# throughHoleAdapterTransistor.net
KiCad netlist of a schematic drawn in EAGLE
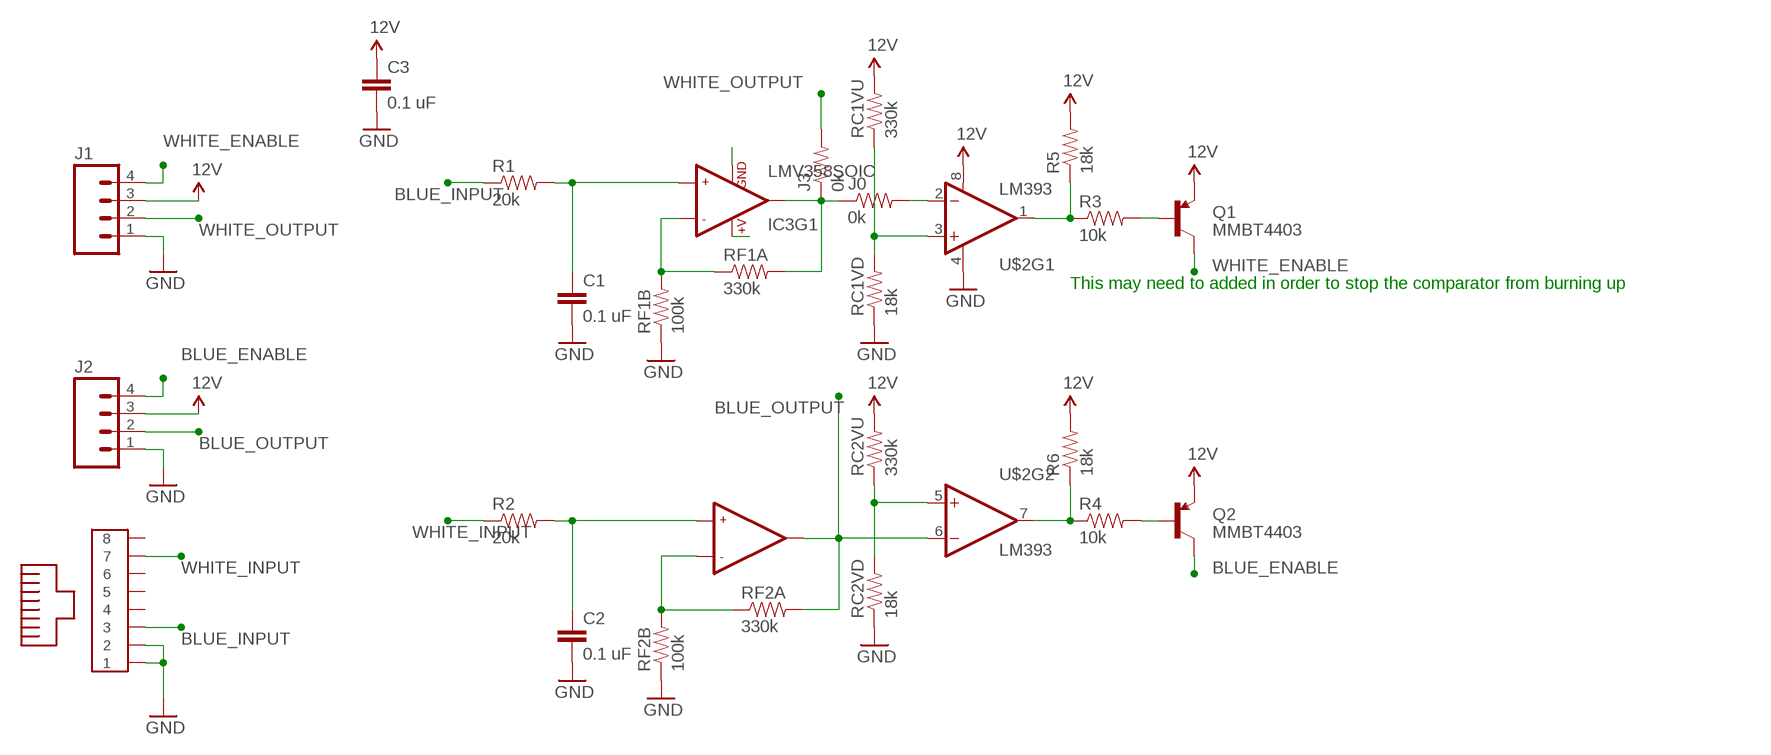
[diagram p0: schematic, sheet 1]

(export (version "E")
  (design (tool "Eeschema 10.0.6"))
  (components
    (comp (ref "C1")
      (value "0.1 uF")
      (footprint "eagle-import:1206")
      (libsource (lib "eagle-import") (part "CAP1206"))
    )
    (comp (ref "C2")
      (value "0.1 uF")
      (footprint "eagle-import:1206")
      (libsource (lib "eagle-import") (part "CAP1206"))
    )
    (comp (ref "C3")
      (value "0.1 uF")
      (footprint "eagle-import:1206")
      (libsource (lib "eagle-import") (part "CAP1206"))
    )
    (comp (ref "IC3")
      (value "LMV358SOIC")
      (footprint "eagle-import:SO08")
      (libsource (lib "eagle-import") (part "LMV358SOIC"))
    )
    (comp (ref "J0")
      (value "0k")
      (footprint "eagle-import:1206")
      (libsource (lib "eagle-import") (part "RESISTOR1206"))
    )
    (comp (ref "J1")
      (value "M04LONGPADS")
      (footprint "eagle-import:1X04_LONGPADS")
      (libsource (lib "eagle-import") (part "M04LONGPADS"))
    )
    (comp (ref "J2")
      (value "M04LONGPADS")
      (footprint "eagle-import:1X04_LONGPADS")
      (libsource (lib "eagle-import") (part "M04LONGPADS"))
    )
    (comp (ref "J3")
      (value "0k")
      (footprint "eagle-import:1206")
      (libsource (lib "eagle-import") (part "RESISTOR1206"))
    )
    (comp (ref "Q1")
      (value "MMBT4403")
      (footprint "eagle-import:SOT23-3")
      (libsource (lib "eagle-import") (part "TRANSISTOR_PNPMMBT4403"))
    )
    (comp (ref "Q2")
      (value "MMBT4403")
      (footprint "eagle-import:SOT23-3")
      (libsource (lib "eagle-import") (part "TRANSISTOR_PNPMMBT4403"))
    )
    (comp (ref "R1")
      (value "20k")
      (footprint "eagle-import:1206")
      (libsource (lib "eagle-import") (part "RESISTOR1206"))
    )
    (comp (ref "R2")
      (value "20k")
      (footprint "eagle-import:1206")
      (libsource (lib "eagle-import") (part "RESISTOR1206"))
    )
    (comp (ref "R3")
      (value "10k")
      (footprint "eagle-import:1206")
      (libsource (lib "eagle-import") (part "RESISTOR1206"))
    )
    (comp (ref "R4")
      (value "10k")
      (footprint "eagle-import:1206")
      (libsource (lib "eagle-import") (part "RESISTOR1206"))
    )
    (comp (ref "R5")
      (value "18k")
      (footprint "eagle-import:1206")
      (libsource (lib "eagle-import") (part "RESISTOR1206"))
    )
    (comp (ref "R6")
      (value "18k")
      (footprint "eagle-import:1206")
      (libsource (lib "eagle-import") (part "RESISTOR1206"))
    )
    (comp (ref "RC1VD")
      (value "18k")
      (footprint "eagle-import:1206")
      (libsource (lib "eagle-import") (part "RESISTOR1206"))
    )
    (comp (ref "RC1VU")
      (value "330k")
      (footprint "eagle-import:1206")
      (libsource (lib "eagle-import") (part "RESISTOR1206"))
    )
    (comp (ref "RC2VD")
      (value "18k")
      (footprint "eagle-import:1206")
      (libsource (lib "eagle-import") (part "RESISTOR1206"))
    )
    (comp (ref "RC2VU")
      (value "330k")
      (footprint "eagle-import:1206")
      (libsource (lib "eagle-import") (part "RESISTOR1206"))
    )
    (comp (ref "RF1A")
      (value "330k")
      (footprint "eagle-import:1206")
      (libsource (lib "eagle-import") (part "RESISTOR1206"))
    )
    (comp (ref "RF1B")
      (value "100k")
      (footprint "eagle-import:1206")
      (libsource (lib "eagle-import") (part "RESISTOR1206"))
    )
    (comp (ref "RF2A")
      (value "330k")
      (footprint "eagle-import:1206")
      (libsource (lib "eagle-import") (part "RESISTOR1206"))
    )
    (comp (ref "RF2B")
      (value "100k")
      (footprint "eagle-import:1206")
      (libsource (lib "eagle-import") (part "RESISTOR1206"))
    )
    (comp (ref "U$1")
      (value "MOLEX-RJ45-SMT")
      (footprint "eagle-import:MOLEX-RJ45-SMT")
      (libsource (lib "eagle-import") (part "MOLEX-RJ45-SMT"))
    )
    (comp (ref "U$2")
      (value "LM393")
      (footprint "eagle-import:SO08")
      (libsource (lib "eagle-import") (part "LM393"))
    )
  )
  (nets
    (net (code "1") (name "/BLUE_ENABLE") (class "Default")
      (node (ref "J2") (pin "4") (pinfunction "4_4") (pintype "passive"))
      (node (ref "Q2") (pin "3") (pinfunction "C_3") (pintype "passive"))
    )
    (net (code "2") (name "/BLUE_INPUT") (class "Default")
      (node (ref "R1") (pin "1") (pinfunction "1_1") (pintype "passive"))
      (node (ref "U$1") (pin "3") (pinfunction "3_3") (pintype "bidirectional"))
    )
    (net (code "3") (name "/BLUE_OUTPUT") (class "Default")
      (node (ref "IC3") (pin "7") (pinfunction "OUT2_7") (pintype "output"))
      (node (ref "J2") (pin "2") (pinfunction "2_2") (pintype "passive"))
      (node (ref "RF2A") (pin "2") (pinfunction "2_2") (pintype "passive"))
      (node (ref "U$2") (pin "6") (pinfunction "-IN_6") (pintype "input"))
    )
    (net (code "4") (name "/WHITE_ENABLE") (class "Default")
      (node (ref "J1") (pin "4") (pinfunction "4_4") (pintype "passive"))
      (node (ref "Q1") (pin "3") (pinfunction "C_3") (pintype "passive"))
    )
    (net (code "5") (name "/WHITE_INPUT") (class "Default")
      (node (ref "R2") (pin "1") (pinfunction "1_1") (pintype "passive"))
      (node (ref "U$1") (pin "7") (pinfunction "7_7") (pintype "bidirectional"))
    )
    (net (code "6") (name "/WHITE_OUTPUT") (class "Default")
      (node (ref "J1") (pin "2") (pinfunction "2_2") (pintype "passive"))
      (node (ref "J3") (pin "2") (pinfunction "2_2") (pintype "passive"))
    )
    (net (code "7") (name "12V") (class "Default")
      (node (ref "C3") (pin "1") (pinfunction "1_1") (pintype "passive"))
      (node (ref "IC3") (pin "8") (pinfunction "+V_8") (pintype "power_in"))
      (node (ref "J1") (pin "3") (pinfunction "3_3") (pintype "passive"))
      (node (ref "J2") (pin "3") (pinfunction "3_3") (pintype "passive"))
      (node (ref "Q1") (pin "2") (pinfunction "E_2") (pintype "passive"))
      (node (ref "Q2") (pin "2") (pinfunction "E_2") (pintype "passive"))
      (node (ref "R5") (pin "2") (pinfunction "2_2") (pintype "passive"))
      (node (ref "R6") (pin "2") (pinfunction "2_2") (pintype "passive"))
      (node (ref "RC1VU") (pin "2") (pinfunction "2_2") (pintype "passive"))
      (node (ref "RC2VU") (pin "2") (pinfunction "2_2") (pintype "passive"))
      (node (ref "U$2") (pin "8") (pinfunction "V+_8") (pintype "power_in"))
    )
    (net (code "8") (name "GND") (class "Default")
      (node (ref "C1") (pin "2") (pinfunction "2_2") (pintype "passive"))
      (node (ref "C2") (pin "2") (pinfunction "2_2") (pintype "passive"))
      (node (ref "C3") (pin "2") (pinfunction "2_2") (pintype "passive"))
      (node (ref "IC3") (pin "4") (pinfunction "GND_4") (pintype "power_in"))
      (node (ref "J1") (pin "1") (pinfunction "1_1") (pintype "passive"))
      (node (ref "J2") (pin "1") (pinfunction "1_1") (pintype "passive"))
      (node (ref "RC1VD") (pin "1") (pinfunction "1_1") (pintype "passive"))
      (node (ref "RC2VD") (pin "1") (pinfunction "1_1") (pintype "passive"))
      (node (ref "RF1B") (pin "1") (pinfunction "1_1") (pintype "passive"))
      (node (ref "RF2B") (pin "1") (pinfunction "1_1") (pintype "passive"))
      (node (ref "U$1") (pin "1") (pinfunction "1_1") (pintype "bidirectional"))
      (node (ref "U$1") (pin "2") (pinfunction "2_2") (pintype "bidirectional"))
      (node (ref "U$2") (pin "4") (pinfunction "V-_4") (pintype "power_in"))
    )
    (net (code "9") (name "Net-(IC3A-+IN1)") (class "Default")
      (node (ref "C1") (pin "1") (pinfunction "1_1") (pintype "passive"))
      (node (ref "IC3") (pin "3") (pinfunction "+IN1_3") (pintype "input"))
      (node (ref "R1") (pin "2") (pinfunction "2_2") (pintype "passive"))
    )
    (net (code "10") (name "Net-(IC3A--IN1)") (class "Default")
      (node (ref "IC3") (pin "2") (pinfunction "-IN1_2") (pintype "input"))
      (node (ref "RF1A") (pin "1") (pinfunction "1_1") (pintype "passive"))
      (node (ref "RF1B") (pin "2") (pinfunction "2_2") (pintype "passive"))
    )
    (net (code "11") (name "Net-(IC3A-OUT1)") (class "Default")
      (node (ref "IC3") (pin "1") (pinfunction "OUT1_1") (pintype "output"))
      (node (ref "J0") (pin "1") (pinfunction "1_1") (pintype "passive"))
      (node (ref "J3") (pin "1") (pinfunction "1_1") (pintype "passive"))
      (node (ref "RF1A") (pin "2") (pinfunction "2_2") (pintype "passive"))
    )
    (net (code "12") (name "Net-(IC3B-+IN2)") (class "Default")
      (node (ref "C2") (pin "1") (pinfunction "1_1") (pintype "passive"))
      (node (ref "IC3") (pin "5") (pinfunction "+IN2_5") (pintype "input"))
      (node (ref "R2") (pin "2") (pinfunction "2_2") (pintype "passive"))
    )
    (net (code "13") (name "Net-(IC3B--IN2)") (class "Default")
      (node (ref "IC3") (pin "6") (pinfunction "-IN2_6") (pintype "input"))
      (node (ref "RF2A") (pin "1") (pinfunction "1_1") (pintype "passive"))
      (node (ref "RF2B") (pin "2") (pinfunction "2_2") (pintype "passive"))
    )
    (net (code "14") (name "Net-(Q1-B)") (class "Default")
      (node (ref "Q1") (pin "1") (pinfunction "B_1") (pintype "passive"))
      (node (ref "R3") (pin "2") (pinfunction "2_2") (pintype "passive"))
    )
    (net (code "15") (name "Net-(Q2-B)") (class "Default")
      (node (ref "Q2") (pin "1") (pinfunction "B_1") (pintype "passive"))
      (node (ref "R4") (pin "2") (pinfunction "2_2") (pintype "passive"))
    )
    (net (code "16") (name "Net-(U$2A-+IN)") (class "Default")
      (node (ref "RC1VD") (pin "2") (pinfunction "2_2") (pintype "passive"))
      (node (ref "RC1VU") (pin "1") (pinfunction "1_1") (pintype "passive"))
      (node (ref "U$2") (pin "3") (pinfunction "+IN_3") (pintype "input"))
    )
    (net (code "17") (name "Net-(U$2A--IN)") (class "Default")
      (node (ref "J0") (pin "2") (pinfunction "2_2") (pintype "passive"))
      (node (ref "U$2") (pin "2") (pinfunction "-IN_2") (pintype "input"))
    )
    (net (code "18") (name "Net-(U$2A-OUT)") (class "Default")
      (node (ref "R3") (pin "1") (pinfunction "1_1") (pintype "passive"))
      (node (ref "R5") (pin "1") (pinfunction "1_1") (pintype "passive"))
      (node (ref "U$2") (pin "1") (pinfunction "OUT_1") (pintype "output"))
    )
    (net (code "19") (name "Net-(U$2B-+IN)") (class "Default")
      (node (ref "RC2VD") (pin "2") (pinfunction "2_2") (pintype "passive"))
      (node (ref "RC2VU") (pin "1") (pinfunction "1_1") (pintype "passive"))
      (node (ref "U$2") (pin "5") (pinfunction "+IN_5") (pintype "input"))
    )
    (net (code "20") (name "Net-(U$2B-OUT)") (class "Default")
      (node (ref "R4") (pin "1") (pinfunction "1_1") (pintype "passive"))
      (node (ref "R6") (pin "1") (pinfunction "1_1") (pintype "passive"))
      (node (ref "U$2") (pin "7") (pinfunction "OUT_7") (pintype "output"))
    )
    (net (code "21") (name "unconnected-(U$1-Pad4)") (class "Default")
      (node (ref "U$1") (pin "4") (pinfunction "4_4") (pintype "bidirectional"))
    )
    (net (code "22") (name "unconnected-(U$1-Pad5)") (class "Default")
      (node (ref "U$1") (pin "5") (pinfunction "5_5") (pintype "bidirectional"))
    )
    (net (code "23") (name "unconnected-(U$1-Pad6)") (class "Default")
      (node (ref "U$1") (pin "6") (pinfunction "6_6") (pintype "bidirectional"))
    )
    (net (code "24") (name "unconnected-(U$1-Pad8)") (class "Default")
      (node (ref "U$1") (pin "8") (pinfunction "8_8") (pintype "bidirectional"))
    )
  )
)
